# LAm-small.net
KiCad netlist of a schematic drawn in EAGLE
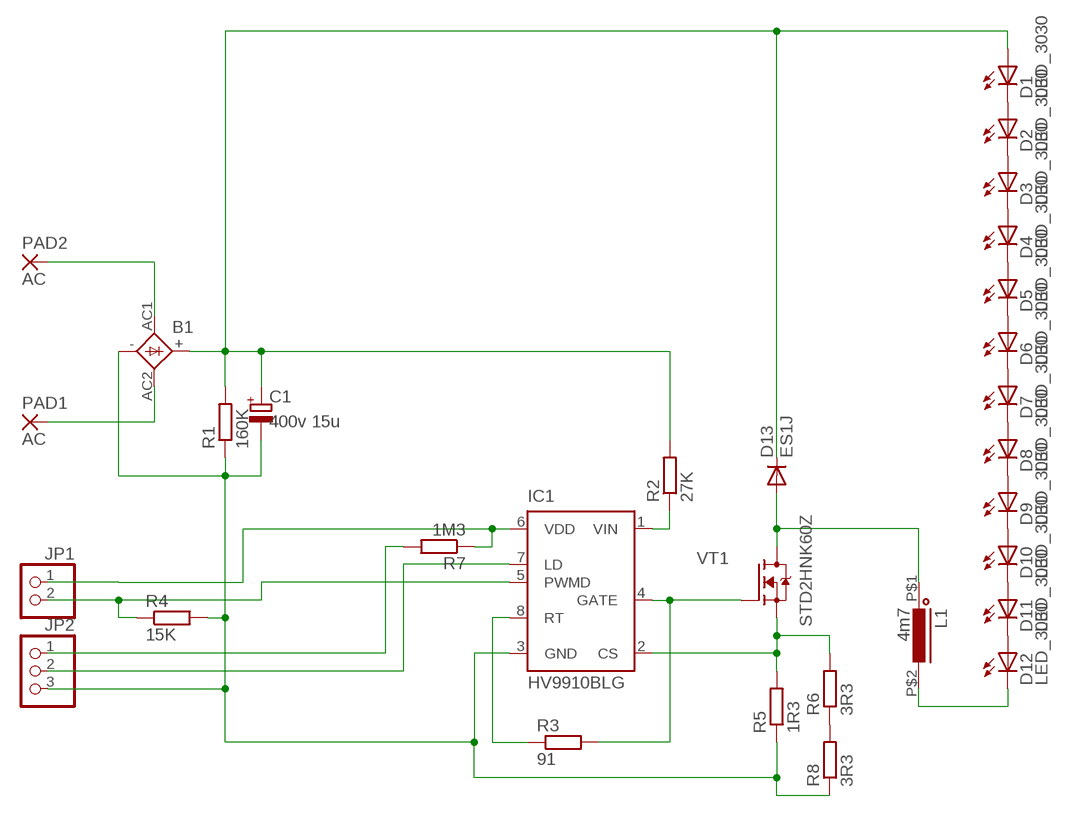
[diagram p0: schematic, sheet 1]

(export (version "E")
  (design (tool "Eeschema 10.0.6"))
  (components
    (comp (ref "B1")
      (value "BRIDGERB1A")
      (footprint "eagle-import:RB1A")
      (libsource (lib "eagle-import") (part "BRIDGERB1A"))
    )
    (comp (ref "C1")
      (value "400v 15u")
      (footprint "eagle-import:E7,5-16-32-HORIZ")
      (libsource (lib "eagle-import") (part "CAP-POL_E7,5-16"))
    )
    (comp (ref "D1")
      (value "LED_3030")
      (footprint "eagle-import:LED3030")
      (libsource (lib "eagle-import") (part "LED_3030"))
    )
    (comp (ref "D2")
      (value "LED_3030")
      (footprint "eagle-import:LED3030")
      (libsource (lib "eagle-import") (part "LED_3030"))
    )
    (comp (ref "D3")
      (value "LED_3030")
      (footprint "eagle-import:LED3030")
      (libsource (lib "eagle-import") (part "LED_3030"))
    )
    (comp (ref "D4")
      (value "LED_3030")
      (footprint "eagle-import:LED3030")
      (libsource (lib "eagle-import") (part "LED_3030"))
    )
    (comp (ref "D5")
      (value "LED_3030")
      (footprint "eagle-import:LED3030")
      (libsource (lib "eagle-import") (part "LED_3030"))
    )
    (comp (ref "D6")
      (value "LED_3030")
      (footprint "eagle-import:LED3030")
      (libsource (lib "eagle-import") (part "LED_3030"))
    )
    (comp (ref "D7")
      (value "LED_3030")
      (footprint "eagle-import:LED3030")
      (libsource (lib "eagle-import") (part "LED_3030"))
    )
    (comp (ref "D8")
      (value "LED_3030")
      (footprint "eagle-import:LED3030")
      (libsource (lib "eagle-import") (part "LED_3030"))
    )
    (comp (ref "D9")
      (value "LED_3030")
      (footprint "eagle-import:LED3030")
      (libsource (lib "eagle-import") (part "LED_3030"))
    )
    (comp (ref "D10")
      (value "LED_3030")
      (footprint "eagle-import:LED3030")
      (libsource (lib "eagle-import") (part "LED_3030"))
    )
    (comp (ref "D11")
      (value "LED_3030")
      (footprint "eagle-import:LED3030")
      (libsource (lib "eagle-import") (part "LED_3030"))
    )
    (comp (ref "D12")
      (value "LED_3030")
      (footprint "eagle-import:LED3030")
      (libsource (lib "eagle-import") (part "LED_3030"))
    )
    (comp (ref "D13")
      (value "ES1J")
      (footprint "eagle-import:DO214AC")
      (libsource (lib "eagle-import") (part "DIODE_ES1J"))
    )
    (comp (ref "IC1")
      (value "HV9910BLG")
      (footprint "eagle-import:SOIC-08LG")
      (fields (field (name "MPN") "MXHV9910B"))
      (libsource (lib "eagle-import") (part "HV9910BLG"))
    )
    (comp (ref "JP1")
      (value "PINHD-1X2/90")
      (footprint "eagle-import:1X02_90")
      (libsource (lib "eagle-import") (part "PINHD-1X2/90"))
    )
    (comp (ref "JP2")
      (value "PINHD-1X3/90")
      (footprint "eagle-import:1X03_90")
      (libsource (lib "eagle-import") (part "PINHD-1X3/90"))
    )
    (comp (ref "L1")
      (value "4m7")
      (footprint "eagle-import:SL1016")
      (libsource (lib "eagle-import") (part "INDUCTORSL1016"))
    )
    (comp (ref "PAD1")
      (value "AC")
      (footprint "eagle-import:3,81_1,4")
      (libsource (lib "eagle-import") (part "3,81/1,4"))
    )
    (comp (ref "PAD2")
      (value "AC")
      (footprint "eagle-import:3,81_1,4")
      (libsource (lib "eagle-import") (part "3,81/1,4"))
    )
    (comp (ref "R1")
      (value "160K")
      (footprint "eagle-import:MF-0125")
      (libsource (lib "eagle-import") (part "R_MF-0125"))
    )
    (comp (ref "R2")
      (value "27K")
      (footprint "eagle-import:MF-2")
      (libsource (lib "eagle-import") (part "R_MF-2"))
    )
    (comp (ref "R3")
      (value "91")
      (footprint "eagle-import:R0805")
      (libsource (lib "eagle-import") (part "R_0805"))
    )
    (comp (ref "R4")
      (value "15K")
      (footprint "eagle-import:R0805")
      (libsource (lib "eagle-import") (part "R_0805"))
    )
    (comp (ref "R5")
      (value "1R3")
      (footprint "eagle-import:KNP-100B")
      (libsource (lib "eagle-import") (part "R_KNP-100B"))
    )
    (comp (ref "R6")
      (value "3R3")
      (footprint "eagle-import:R0805")
      (libsource (lib "eagle-import") (part "R_0805"))
    )
    (comp (ref "R7")
      (value "1M3")
      (footprint "eagle-import:R0805")
      (libsource (lib "eagle-import") (part "R_0805"))
    )
    (comp (ref "R8")
      (value "3R3")
      (footprint "eagle-import:R0805")
      (libsource (lib "eagle-import") (part "R_0805"))
    )
    (comp (ref "VT1")
      (value "STD2HNK60Z")
      (footprint "eagle-import:DPAK")
      (libsource (lib "eagle-import") (part "FET-NDPAK"))
    )
  )
  (nets
    (net (code "1") (name "Net-(D1-A)") (class "Default")
      (node (ref "B1") (pin "+") (pinfunction "+_+") (pintype "passive"))
      (node (ref "C1") (pin "+") (pinfunction "+_+") (pintype "passive"))
      (node (ref "D1") (pin "P$1") (pinfunction "A_P$1") (pintype "passive"))
      (node (ref "D13") (pin "C") (pinfunction "C_C") (pintype "passive"))
      (node (ref "R1") (pin "2") (pinfunction "2_2") (pintype "passive"))
      (node (ref "R2") (pin "2") (pinfunction "2_2") (pintype "passive"))
    )
    (net (code "2") (name "Net-(D1-C)") (class "Default")
      (node (ref "D1") (pin "P$2") (pinfunction "C_P$2") (pintype "passive"))
      (node (ref "D2") (pin "P$1") (pinfunction "A_P$1") (pintype "passive"))
    )
    (net (code "3") (name "Net-(D2-C)") (class "Default")
      (node (ref "D2") (pin "P$2") (pinfunction "C_P$2") (pintype "passive"))
      (node (ref "D3") (pin "P$1") (pinfunction "A_P$1") (pintype "passive"))
    )
    (net (code "4") (name "Net-(D3-C)") (class "Default")
      (node (ref "D3") (pin "P$2") (pinfunction "C_P$2") (pintype "passive"))
      (node (ref "D4") (pin "P$1") (pinfunction "A_P$1") (pintype "passive"))
    )
    (net (code "5") (name "Net-(D4-C)") (class "Default")
      (node (ref "D4") (pin "P$2") (pinfunction "C_P$2") (pintype "passive"))
      (node (ref "D5") (pin "P$1") (pinfunction "A_P$1") (pintype "passive"))
    )
    (net (code "6") (name "Net-(D5-C)") (class "Default")
      (node (ref "D5") (pin "P$2") (pinfunction "C_P$2") (pintype "passive"))
      (node (ref "D6") (pin "P$1") (pinfunction "A_P$1") (pintype "passive"))
    )
    (net (code "7") (name "Net-(D6-C)") (class "Default")
      (node (ref "D6") (pin "P$2") (pinfunction "C_P$2") (pintype "passive"))
      (node (ref "D7") (pin "P$1") (pinfunction "A_P$1") (pintype "passive"))
    )
    (net (code "8") (name "Net-(D7-C)") (class "Default")
      (node (ref "D7") (pin "P$2") (pinfunction "C_P$2") (pintype "passive"))
      (node (ref "D8") (pin "P$1") (pinfunction "A_P$1") (pintype "passive"))
    )
    (net (code "9") (name "Net-(D8-C)") (class "Default")
      (node (ref "D8") (pin "P$2") (pinfunction "C_P$2") (pintype "passive"))
      (node (ref "D9") (pin "P$1") (pinfunction "A_P$1") (pintype "passive"))
    )
    (net (code "10") (name "Net-(D10-A)") (class "Default")
      (node (ref "D10") (pin "P$1") (pinfunction "A_P$1") (pintype "passive"))
      (node (ref "D9") (pin "P$2") (pinfunction "C_P$2") (pintype "passive"))
    )
    (net (code "11") (name "Net-(D10-C)") (class "Default")
      (node (ref "D10") (pin "P$2") (pinfunction "C_P$2") (pintype "passive"))
      (node (ref "D11") (pin "P$1") (pinfunction "A_P$1") (pintype "passive"))
    )
    (net (code "12") (name "Net-(D11-C)") (class "Default")
      (node (ref "D11") (pin "P$2") (pinfunction "C_P$2") (pintype "passive"))
      (node (ref "D12") (pin "P$1") (pinfunction "A_P$1") (pintype "passive"))
    )
    (net (code "13") (name "Net-(D12-C)") (class "Default")
      (node (ref "D12") (pin "P$2") (pinfunction "C_P$2") (pintype "passive"))
      (node (ref "L1") (pin "P$2") (pinfunction "2_P$2") (pintype "passive"))
    )
    (net (code "14") (name "Net-(IC1-CS)") (class "Default")
      (node (ref "IC1") (pin "2") (pinfunction "CS_2") (pintype "input"))
      (node (ref "R5") (pin "2") (pinfunction "2_2") (pintype "passive"))
      (node (ref "R6") (pin "2") (pinfunction "2_2") (pintype "passive"))
      (node (ref "VT1") (pin "S") (pinfunction "S_S") (pintype "passive"))
    )
    (net (code "15") (name "Net-(IC1-GATE)") (class "Default")
      (node (ref "IC1") (pin "4") (pinfunction "GATE_4") (pintype "output"))
      (node (ref "R3") (pin "2") (pinfunction "2_2") (pintype "passive"))
      (node (ref "VT1") (pin "G") (pinfunction "G_G") (pintype "passive"))
    )
    (net (code "16") (name "Net-(IC1-GND)") (class "Default")
      (node (ref "B1") (pin "-") (pinfunction "-_-") (pintype "passive"))
      (node (ref "C1") (pin "-") (pinfunction "-_-") (pintype "passive"))
      (node (ref "IC1") (pin "3") (pinfunction "GND_3") (pintype "power_in"))
      (node (ref "JP2") (pin "3") (pinfunction "3_3") (pintype "passive"))
      (node (ref "R1") (pin "1") (pinfunction "1_1") (pintype "passive"))
      (node (ref "R4") (pin "2") (pinfunction "2_2") (pintype "passive"))
      (node (ref "R5") (pin "1") (pinfunction "1_1") (pintype "passive"))
      (node (ref "R8") (pin "1") (pinfunction "1_1") (pintype "passive"))
    )
    (net (code "17") (name "Net-(IC1-LD)") (class "Default")
      (node (ref "IC1") (pin "7") (pinfunction "LD_7") (pintype "input"))
      (node (ref "JP2") (pin "2") (pinfunction "2_2") (pintype "passive"))
    )
    (net (code "18") (name "Net-(IC1-PWMD)") (class "Default")
      (node (ref "IC1") (pin "5") (pinfunction "PWMD_5") (pintype "input"))
      (node (ref "JP1") (pin "2") (pinfunction "2_2") (pintype "passive"))
      (node (ref "R4") (pin "1") (pinfunction "1_1") (pintype "passive"))
    )
    (net (code "19") (name "Net-(IC1-RT)") (class "Default")
      (node (ref "IC1") (pin "8") (pinfunction "RT_8") (pintype "passive"))
      (node (ref "R3") (pin "1") (pinfunction "1_1") (pintype "passive"))
    )
    (net (code "20") (name "Net-(IC1-VDD)") (class "Default")
      (node (ref "IC1") (pin "6") (pinfunction "VDD_6") (pintype "power_in"))
      (node (ref "JP1") (pin "1") (pinfunction "1_1") (pintype "passive"))
      (node (ref "R7") (pin "1") (pinfunction "1_1") (pintype "passive"))
    )
    (net (code "21") (name "Net-(IC1-VIN)") (class "Default")
      (node (ref "IC1") (pin "1") (pinfunction "VIN_1") (pintype "input"))
      (node (ref "R2") (pin "1") (pinfunction "1_1") (pintype "passive"))
    )
    (net (code "22") (name "Net-(JP2-Pad1)") (class "Default")
      (node (ref "JP2") (pin "1") (pinfunction "1_1") (pintype "passive"))
      (node (ref "R7") (pin "2") (pinfunction "2_2") (pintype "passive"))
    )
    (net (code "23") (name "Net-(L1-1)") (class "Default")
      (node (ref "D13") (pin "A") (pinfunction "A_A") (pintype "passive"))
      (node (ref "L1") (pin "P$1") (pinfunction "1_P$1") (pintype "passive"))
      (node (ref "VT1") (pin "D") (pinfunction "D_D") (pintype "passive"))
    )
    (net (code "24") (name "Net-(PAD1-P)") (class "Default")
      (node (ref "B1") (pin "AC2") (pinfunction "AC2_AC2") (pintype "passive"))
      (node (ref "PAD1") (pin "1") (pinfunction "P_1") (pintype "passive"))
    )
    (net (code "25") (name "Net-(PAD2-P)") (class "Default")
      (node (ref "B1") (pin "AC1") (pinfunction "AC1_AC1") (pintype "passive"))
      (node (ref "PAD2") (pin "1") (pinfunction "P_1") (pintype "passive"))
    )
    (net (code "26") (name "Net-(R6-Pad1)") (class "Default")
      (node (ref "R6") (pin "1") (pinfunction "1_1") (pintype "passive"))
      (node (ref "R8") (pin "2") (pinfunction "2_2") (pintype "passive"))
    )
  )
)
